# controller.net
KiCad netlist of a schematic drawn in Altium Designer
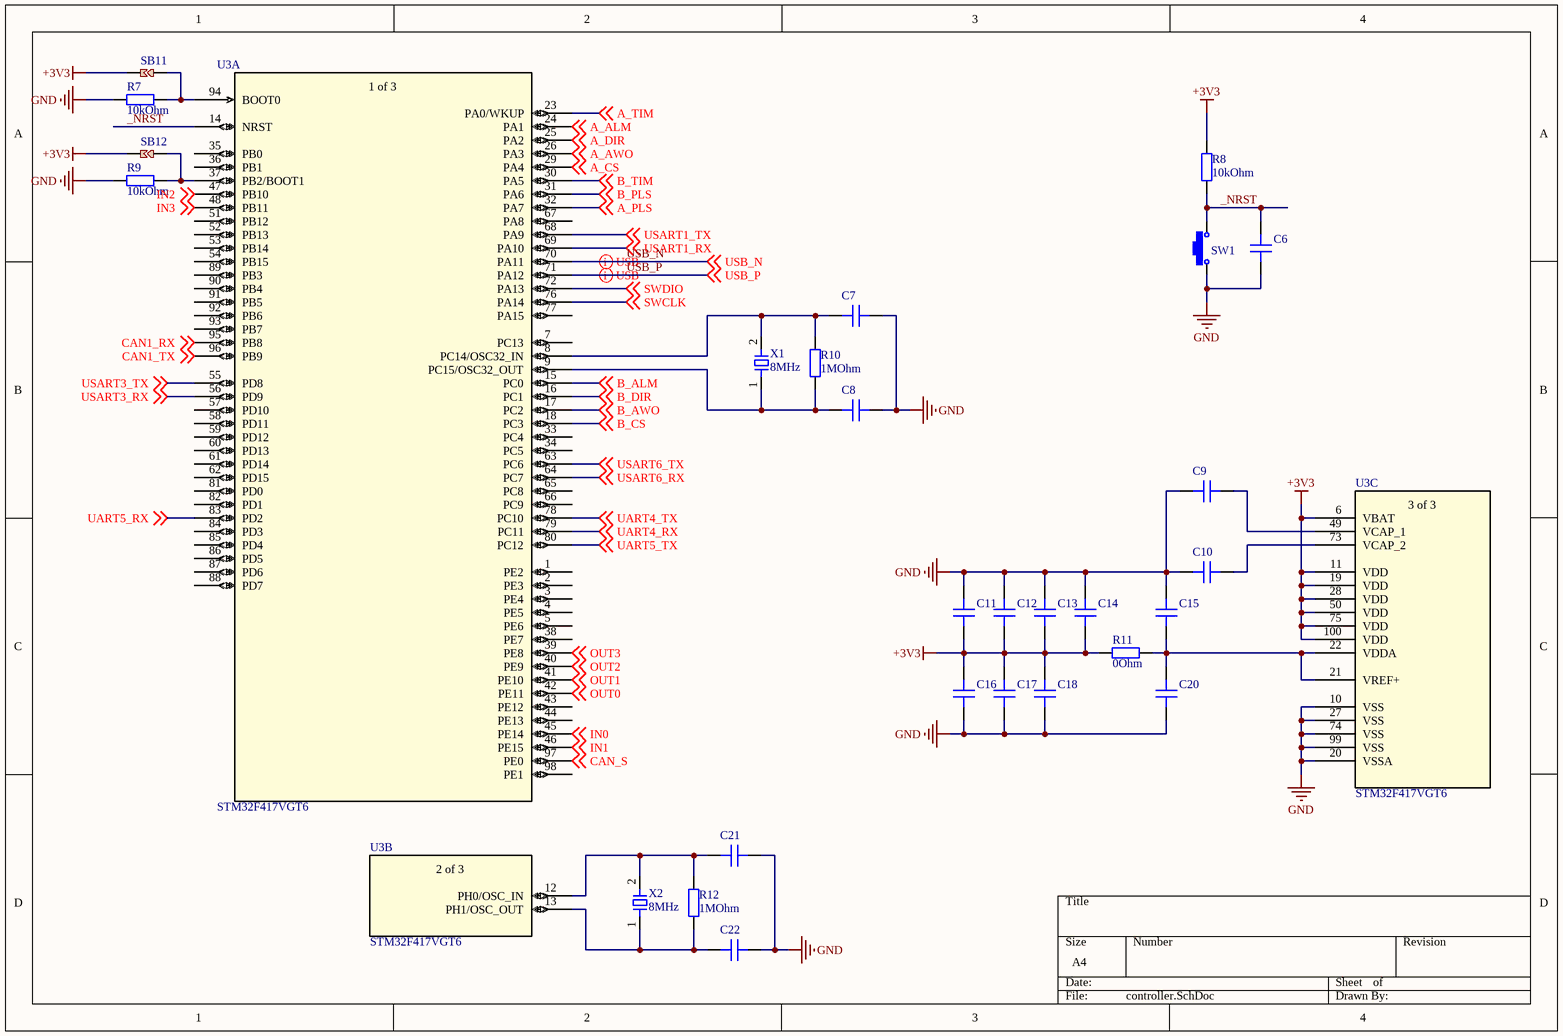
[diagram p0: controller.SchDoc]

(export (version "E")
  (design (tool "Eeschema 10.0.6"))
  (components
    (comp (ref "C6")
      (value "100nF")
      (footprint "CAP 0805")
      (description "Non-polar capacitor")
      (fields (field (name "PUBLISHER") "Altium Limited"))
      (libsource (lib "MiLib") (part "Cap"))
    )
    (comp (ref "C7")
      (value "100nF")
      (footprint "CAP 0805")
      (description "Non-polar capacitor")
      (fields (field (name "PUBLISHER") "Altium Limited"))
      (libsource (lib "MiLib") (part "Cap"))
    )
    (comp (ref "C8")
      (value "100nF")
      (footprint "CAP 0805")
      (description "Non-polar capacitor")
      (fields (field (name "PUBLISHER") "Altium Limited"))
      (libsource (lib "MiLib") (part "Cap"))
    )
    (comp (ref "C9")
      (value "100nF")
      (footprint "CAP 0805")
      (description "Non-polar capacitor")
      (fields (field (name "PUBLISHER") "Altium Limited"))
      (libsource (lib "MiLib") (part "Cap"))
    )
    (comp (ref "C10")
      (value "100nF")
      (footprint "CAP 0805")
      (description "Non-polar capacitor")
      (fields (field (name "PUBLISHER") "Altium Limited"))
      (libsource (lib "MiLib") (part "Cap"))
    )
    (comp (ref "C11")
      (value "100nF")
      (footprint "CAP 0805")
      (description "Non-polar capacitor")
      (fields (field (name "PUBLISHER") "Altium Limited"))
      (libsource (lib "MiLib") (part "Cap"))
    )
    (comp (ref "C12")
      (value "100nF")
      (footprint "CAP 0805")
      (description "Non-polar capacitor")
      (fields (field (name "PUBLISHER") "Altium Limited"))
      (libsource (lib "MiLib") (part "Cap"))
    )
    (comp (ref "C13")
      (value "100nF")
      (footprint "CAP 0805")
      (description "Non-polar capacitor")
      (fields (field (name "PUBLISHER") "Altium Limited"))
      (libsource (lib "MiLib") (part "Cap"))
    )
    (comp (ref "C14")
      (value "100nF")
      (footprint "CAP 0805")
      (description "Non-polar capacitor")
      (fields (field (name "PUBLISHER") "Altium Limited"))
      (libsource (lib "MiLib") (part "Cap"))
    )
    (comp (ref "C15")
      (value "100nF")
      (footprint "CAP 0805")
      (description "Non-polar capacitor")
      (fields (field (name "PUBLISHER") "Altium Limited"))
      (libsource (lib "MiLib") (part "Cap"))
    )
    (comp (ref "C16")
      (value "100nF")
      (footprint "CAP 0805")
      (description "Non-polar capacitor")
      (fields (field (name "PUBLISHER") "Altium Limited"))
      (libsource (lib "MiLib") (part "Cap"))
    )
    (comp (ref "C17")
      (value "100nF")
      (footprint "CAP 0805")
      (description "Non-polar capacitor")
      (fields (field (name "PUBLISHER") "Altium Limited"))
      (libsource (lib "MiLib") (part "Cap"))
    )
    (comp (ref "C18")
      (value "100nF")
      (footprint "CAP 0805")
      (description "Non-polar capacitor")
      (fields (field (name "PUBLISHER") "Altium Limited"))
      (libsource (lib "MiLib") (part "Cap"))
    )
    (comp (ref "C20")
      (value "100nF")
      (footprint "CAP 0805")
      (description "Non-polar capacitor")
      (fields (field (name "PUBLISHER") "Altium Limited"))
      (libsource (lib "MiLib") (part "Cap"))
    )
    (comp (ref "C21")
      (value "100nF")
      (footprint "CAP 0805")
      (description "Non-polar capacitor")
      (fields (field (name "PUBLISHER") "Altium Limited"))
      (libsource (lib "MiLib") (part "Cap"))
    )
    (comp (ref "C22")
      (value "100nF")
      (footprint "CAP 0805")
      (description "Non-polar capacitor")
      (fields (field (name "PUBLISHER") "Altium Limited"))
      (libsource (lib "MiLib") (part "Cap"))
    )
    (comp (ref "R7")
      (value "10kOhm")
      (footprint "RES 0805")
      (description "Resistor")
      (fields (field (name "PUBLISHER") "Altium Limited"))
      (libsource (lib "") (part "Res_1"))
    )
    (comp (ref "R8")
      (value "10kOhm")
      (footprint "RES 0805")
      (description "Resistor")
      (fields (field (name "PUBLISHER") "Altium Limited"))
      (libsource (lib "MiLib") (part "Res"))
    )
    (comp (ref "R9")
      (value "10kOhm")
      (footprint "RES 0805")
      (description "Resistor")
      (fields (field (name "PUBLISHER") "Altium Limited"))
      (libsource (lib "") (part "Res_1"))
    )
    (comp (ref "R10")
      (value "1MOhm")
      (footprint "RES 0805")
      (description "Resistor")
      (fields (field (name "PUBLISHER") "Altium Limited"))
      (libsource (lib "MiLib") (part "Res"))
    )
    (comp (ref "R11")
      (value "0Ohm")
      (footprint "RES 0805")
      (description "Resistor")
      (fields (field (name "PUBLISHER") "Altium Limited"))
      (libsource (lib "") (part "Res_2"))
    )
    (comp (ref "R12")
      (value "1MOhm")
      (footprint "RES 0805")
      (description "Resistor")
      (fields (field (name "PUBLISHER") "Altium Limited"))
      (libsource (lib "MiLib") (part "Res"))
    )
    (comp (ref "SB11") (value "SB") (footprint "Solder Bridge") (libsource (lib "MiLib") (part "SB")))
    (comp (ref "SB12") (value "SB") (footprint "Solder Bridge") (libsource (lib "MiLib") (part "SB")))
    (comp (ref "SW1")
      (value "Button")
      (footprint "TSW SMD-3*6*2.5")
      (fields (field (name "版权归属") "黎明电子style"))
      (libsource (lib "MiLib") (part "BTN"))
    )
    (comp (ref "U3")
      (value "STM32F417VGT6")
      (footprint "LQFP100-14×14mm")
      (description "No Description Available")
      (fields (field (name "COPYRIGHT") "Copyright (C) 2018 Accelerated Designs. All rights reserved"))
      (libsource (lib "misc") (part "STM32F417VGT6"))
    )
    (comp (ref "X1")
      (value "8MHz")
      (footprint "XTAL 3215")
      (description "Passive Oscillator")
      (fields (field (name "版权归属") "黎明电子style"))
      (libsource (lib "MiLib") (part "XTAL"))
    )
    (comp (ref "X2")
      (value "8MHz")
      (footprint "XTAL 3225")
      (description "Passive Oscillator")
      (fields (field (name "版权归属") "黎明电子style"))
      (libsource (lib "MiLib") (part "XTAL"))
    )
  )
  (nets
    (net (code "1") (name "+3V3") (class "Default")
      (node (ref "C11") (pin "1") (pinfunction "1_1") (pintype "passive"))
      (node (ref "C12") (pin "1") (pinfunction "1_1") (pintype "passive"))
      (node (ref "C13") (pin "1") (pinfunction "1_1") (pintype "passive"))
      (node (ref "C14") (pin "1") (pinfunction "1_1") (pintype "passive"))
      (node (ref "C16") (pin "2") (pinfunction "2_2") (pintype "passive"))
      (node (ref "C17") (pin "2") (pinfunction "2_2") (pintype "passive"))
      (node (ref "C18") (pin "2") (pinfunction "2_2") (pintype "passive"))
      (node (ref "R11") (pin "1") (pinfunction "1_1") (pintype "passive"))
      (node (ref "R8") (pin "2") (pinfunction "2_2") (pintype "passive"))
      (node (ref "SB11") (pin "1") (pinfunction "1_1") (pintype "passive"))
      (node (ref "SB12") (pin "1") (pinfunction "1_1") (pintype "passive"))
      (node (ref "U3") (pin "100") (pinfunction "VDD_100") (pintype "power_in"))
      (node (ref "U3") (pin "11") (pinfunction "VDD_11") (pintype "power_in"))
      (node (ref "U3") (pin "19") (pinfunction "VDD_19") (pintype "power_in"))
      (node (ref "U3") (pin "28") (pinfunction "VDD_28") (pintype "power_in"))
      (node (ref "U3") (pin "50") (pinfunction "VDD_50") (pintype "power_in"))
      (node (ref "U3") (pin "6") (pinfunction "VBAT_6") (pintype "power_in"))
      (node (ref "U3") (pin "75") (pinfunction "VDD_75") (pintype "power_in"))
    )
    (net (code "2") (name "/_NRST") (class "Default")
      (node (ref "C6") (pin "2") (pinfunction "2_2") (pintype "passive"))
      (node (ref "R8") (pin "1") (pinfunction "1_1") (pintype "passive"))
      (node (ref "SW1") (pin "2") (pinfunction "2_2") (pintype "passive"))
      (node (ref "U3") (pin "14") (pinfunction "NRST_14") (pintype "bidirectional"))
    )
    (net (code "3") (name "A_ALM") (class "Default")
      (node (ref "U3") (pin "24") (pinfunction "PA1_24") (pintype "bidirectional"))
    )
    (net (code "4") (name "A_AWO") (class "Default")
      (node (ref "U3") (pin "26") (pinfunction "PA3_26") (pintype "bidirectional"))
    )
    (net (code "5") (name "A_CS") (class "Default")
      (node (ref "U3") (pin "29") (pinfunction "PA4_29") (pintype "bidirectional"))
    )
    (net (code "6") (name "A_DIR") (class "Default")
      (node (ref "U3") (pin "25") (pinfunction "PA2_25") (pintype "bidirectional"))
    )
    (net (code "7") (name "A_PLS") (class "Default")
      (node (ref "U3") (pin "32") (pinfunction "PA7_32") (pintype "bidirectional"))
    )
    (net (code "8") (name "A_TIM") (class "Default")
      (node (ref "U3") (pin "23") (pinfunction "PA0/WKUP_23") (pintype "bidirectional"))
    )
    (net (code "9") (name "B_ALM") (class "Default")
      (node (ref "U3") (pin "15") (pinfunction "PC0_15") (pintype "bidirectional"))
    )
    (net (code "10") (name "B_AWO") (class "Default")
      (node (ref "U3") (pin "17") (pinfunction "PC2_17") (pintype "bidirectional"))
    )
    (net (code "11") (name "B_CS") (class "Default")
      (node (ref "U3") (pin "18") (pinfunction "PC3_18") (pintype "bidirectional"))
    )
    (net (code "12") (name "B_DIR") (class "Default")
      (node (ref "U3") (pin "16") (pinfunction "PC1_16") (pintype "bidirectional"))
    )
    (net (code "13") (name "B_PLS") (class "Default")
      (node (ref "U3") (pin "31") (pinfunction "PA6_31") (pintype "bidirectional"))
    )
    (net (code "14") (name "B_TIM") (class "Default")
      (node (ref "U3") (pin "30") (pinfunction "PA5_30") (pintype "bidirectional"))
    )
    (net (code "15") (name "CAN1_RX") (class "Default")
      (node (ref "U3") (pin "95") (pinfunction "PB8_95") (pintype "bidirectional"))
    )
    (net (code "16") (name "CAN1_TX") (class "Default")
      (node (ref "U3") (pin "96") (pinfunction "PB9_96") (pintype "bidirectional"))
    )
    (net (code "17") (name "CAN_S") (class "Default")
      (node (ref "U3") (pin "97") (pinfunction "PE0_97") (pintype "bidirectional"))
    )
    (net (code "18") (name "GND") (class "Default")
      (node (ref "C10") (pin "2") (pinfunction "2_2") (pintype "passive"))
      (node (ref "C11") (pin "2") (pinfunction "2_2") (pintype "passive"))
      (node (ref "C12") (pin "2") (pinfunction "2_2") (pintype "passive"))
      (node (ref "C13") (pin "2") (pinfunction "2_2") (pintype "passive"))
      (node (ref "C14") (pin "2") (pinfunction "2_2") (pintype "passive"))
      (node (ref "C15") (pin "2") (pinfunction "2_2") (pintype "passive"))
      (node (ref "C16") (pin "1") (pinfunction "1_1") (pintype "passive"))
      (node (ref "C17") (pin "1") (pinfunction "1_1") (pintype "passive"))
      (node (ref "C18") (pin "1") (pinfunction "1_1") (pintype "passive"))
      (node (ref "C20") (pin "1") (pinfunction "1_1") (pintype "passive"))
      (node (ref "C21") (pin "2") (pinfunction "2_2") (pintype "passive"))
      (node (ref "C22") (pin "2") (pinfunction "2_2") (pintype "passive"))
      (node (ref "C6") (pin "1") (pinfunction "1_1") (pintype "passive"))
      (node (ref "C7") (pin "2") (pinfunction "2_2") (pintype "passive"))
      (node (ref "C8") (pin "2") (pinfunction "2_2") (pintype "passive"))
      (node (ref "C9") (pin "2") (pinfunction "2_2") (pintype "passive"))
      (node (ref "R7") (pin "2") (pinfunction "2_2") (pintype "passive"))
      (node (ref "R9") (pin "2") (pinfunction "2_2") (pintype "passive"))
      (node (ref "SW1") (pin "1") (pinfunction "1_1") (pintype "passive"))
      (node (ref "U3") (pin "10") (pinfunction "VSS_10") (pintype "power_in"))
      (node (ref "U3") (pin "20") (pinfunction "VSSA_20") (pintype "power_in"))
      (node (ref "U3") (pin "27") (pinfunction "VSS_27") (pintype "power_in"))
      (node (ref "U3") (pin "74") (pinfunction "VSS_74") (pintype "power_in"))
      (node (ref "U3") (pin "99") (pinfunction "VSS_99") (pintype "power_in"))
    )
    (net (code "19") (name "IN0") (class "Default")
      (node (ref "U3") (pin "45") (pinfunction "PE14_45") (pintype "bidirectional"))
    )
    (net (code "20") (name "IN1") (class "Default")
      (node (ref "U3") (pin "46") (pinfunction "PE15_46") (pintype "bidirectional"))
    )
    (net (code "21") (name "IN2") (class "Default")
      (node (ref "U3") (pin "47") (pinfunction "PB10_47") (pintype "bidirectional"))
    )
    (net (code "22") (name "IN3") (class "Default")
      (node (ref "U3") (pin "48") (pinfunction "PB11_48") (pintype "bidirectional"))
    )
    (net (code "23") (name "Net-(U3A-BOOT0)") (class "Default")
      (node (ref "R7") (pin "1") (pinfunction "1_1") (pintype "passive"))
      (node (ref "SB11") (pin "2") (pinfunction "2_2") (pintype "passive"))
      (node (ref "U3") (pin "94") (pinfunction "BOOT0_94") (pintype "input"))
    )
    (net (code "24") (name "Net-(U3A-PB2{slash}BOOT1)") (class "Default")
      (node (ref "R9") (pin "1") (pinfunction "1_1") (pintype "passive"))
      (node (ref "SB12") (pin "2") (pinfunction "2_2") (pintype "passive"))
      (node (ref "U3") (pin "37") (pinfunction "PB2/BOOT1_37") (pintype "bidirectional"))
    )
    (net (code "25") (name "Net-(U3A-PC14{slash}OSC32_IN)") (class "Default")
      (node (ref "C7") (pin "1") (pinfunction "1_1") (pintype "passive"))
      (node (ref "R10") (pin "2") (pinfunction "2_2") (pintype "passive"))
      (node (ref "U3") (pin "8") (pinfunction "PC14/OSC32_IN_8") (pintype "bidirectional"))
      (node (ref "X1") (pin "2") (pinfunction "2_2") (pintype "passive"))
    )
    (net (code "26") (name "Net-(U3A-PC15{slash}OSC32_OUT)") (class "Default")
      (node (ref "C8") (pin "1") (pinfunction "1_1") (pintype "passive"))
      (node (ref "R10") (pin "1") (pinfunction "1_1") (pintype "passive"))
      (node (ref "U3") (pin "9") (pinfunction "PC15/OSC32_OUT_9") (pintype "bidirectional"))
      (node (ref "X1") (pin "1") (pinfunction "1_1") (pintype "passive"))
    )
    (net (code "27") (name "Net-(U3B-PH0{slash}OSC_IN)") (class "Default")
      (node (ref "C21") (pin "1") (pinfunction "1_1") (pintype "passive"))
      (node (ref "R12") (pin "2") (pinfunction "2_2") (pintype "passive"))
      (node (ref "U3") (pin "12") (pinfunction "PH0/OSC_IN_12") (pintype "bidirectional"))
      (node (ref "X2") (pin "2") (pinfunction "2_2") (pintype "passive"))
    )
    (net (code "28") (name "Net-(U3B-PH1{slash}OSC_OUT)") (class "Default")
      (node (ref "C22") (pin "1") (pinfunction "1_1") (pintype "passive"))
      (node (ref "R12") (pin "1") (pinfunction "1_1") (pintype "passive"))
      (node (ref "U3") (pin "13") (pinfunction "PH1/OSC_OUT_13") (pintype "bidirectional"))
      (node (ref "X2") (pin "1") (pinfunction "1_1") (pintype "passive"))
    )
    (net (code "29") (name "Net-(U3C-VCAP_1)") (class "Default")
      (node (ref "C9") (pin "1") (pinfunction "1_1") (pintype "passive"))
      (node (ref "U3") (pin "49") (pinfunction "VCAP_1_49") (pintype "power_in"))
    )
    (net (code "30") (name "Net-(U3C-VCAP_2)") (class "Default")
      (node (ref "C10") (pin "1") (pinfunction "1_1") (pintype "passive"))
      (node (ref "U3") (pin "73") (pinfunction "VCAP_2_73") (pintype "power_in"))
    )
    (net (code "31") (name "Net-(U3C-VDDA)") (class "Default")
      (node (ref "C15") (pin "1") (pinfunction "1_1") (pintype "passive"))
      (node (ref "C20") (pin "2") (pinfunction "2_2") (pintype "passive"))
      (node (ref "R11") (pin "2") (pinfunction "2_2") (pintype "passive"))
      (node (ref "U3") (pin "21") (pinfunction "VREF+_21") (pintype "power_in"))
      (node (ref "U3") (pin "22") (pinfunction "VDDA_22") (pintype "power_in"))
    )
    (net (code "32") (name "OUT0") (class "Default")
      (node (ref "U3") (pin "42") (pinfunction "PE11_42") (pintype "bidirectional"))
    )
    (net (code "33") (name "OUT1") (class "Default")
      (node (ref "U3") (pin "41") (pinfunction "PE10_41") (pintype "bidirectional"))
    )
    (net (code "34") (name "OUT2") (class "Default")
      (node (ref "U3") (pin "40") (pinfunction "PE9_40") (pintype "bidirectional"))
    )
    (net (code "35") (name "OUT3") (class "Default")
      (node (ref "U3") (pin "39") (pinfunction "PE8_39") (pintype "bidirectional"))
    )
    (net (code "36") (name "SWCLK") (class "Default")
      (node (ref "U3") (pin "76") (pinfunction "PA14_76") (pintype "bidirectional"))
    )
    (net (code "37") (name "SWDIO") (class "Default")
      (node (ref "U3") (pin "72") (pinfunction "PA13_72") (pintype "bidirectional"))
    )
    (net (code "38") (name "UART4_RX") (class "Default")
      (node (ref "U3") (pin "79") (pinfunction "PC11_79") (pintype "bidirectional"))
    )
    (net (code "39") (name "UART4_TX") (class "Default")
      (node (ref "U3") (pin "78") (pinfunction "PC10_78") (pintype "bidirectional"))
    )
    (net (code "40") (name "UART5_RX") (class "Default")
      (node (ref "U3") (pin "83") (pinfunction "PD2_83") (pintype "bidirectional"))
    )
    (net (code "41") (name "UART5_TX") (class "Default")
      (node (ref "U3") (pin "80") (pinfunction "PC12_80") (pintype "bidirectional"))
    )
    (net (code "42") (name "USART1_RX") (class "Default")
      (node (ref "U3") (pin "69") (pinfunction "PA10_69") (pintype "bidirectional"))
    )
    (net (code "43") (name "USART1_TX") (class "Default")
      (node (ref "U3") (pin "68") (pinfunction "PA9_68") (pintype "bidirectional"))
    )
    (net (code "44") (name "USART3_RX") (class "Default")
      (node (ref "U3") (pin "56") (pinfunction "PD9_56") (pintype "bidirectional"))
    )
    (net (code "45") (name "USART3_TX") (class "Default")
      (node (ref "U3") (pin "55") (pinfunction "PD8_55") (pintype "bidirectional"))
    )
    (net (code "46") (name "USART6_RX") (class "Default")
      (node (ref "U3") (pin "64") (pinfunction "PC7_64") (pintype "bidirectional"))
    )
    (net (code "47") (name "USART6_TX") (class "Default")
      (node (ref "U3") (pin "63") (pinfunction "PC6_63") (pintype "bidirectional"))
    )
    (net (code "48") (name "USB_N") (class "Default")
      (node (ref "U3") (pin "70") (pinfunction "PA11_70") (pintype "bidirectional"))
    )
    (net (code "49") (name "USB_P") (class "Default")
      (node (ref "U3") (pin "71") (pinfunction "PA12_71") (pintype "bidirectional"))
    )
    (net (code "50") (name "unconnected-(U3A-PA8-Pad67)") (class "Default")
      (node (ref "U3") (pin "67") (pinfunction "PA8_67") (pintype "bidirectional"))
    )
    (net (code "51") (name "unconnected-(U3A-PA15-Pad77)") (class "Default")
      (node (ref "U3") (pin "77") (pinfunction "PA15_77") (pintype "bidirectional"))
    )
    (net (code "52") (name "unconnected-(U3A-PB0-Pad35)") (class "Default")
      (node (ref "U3") (pin "35") (pinfunction "PB0_35") (pintype "bidirectional"))
    )
    (net (code "53") (name "unconnected-(U3A-PB1-Pad36)") (class "Default")
      (node (ref "U3") (pin "36") (pinfunction "PB1_36") (pintype "bidirectional"))
    )
    (net (code "54") (name "unconnected-(U3A-PB3-Pad89)") (class "Default")
      (node (ref "U3") (pin "89") (pinfunction "PB3_89") (pintype "bidirectional"))
    )
    (net (code "55") (name "unconnected-(U3A-PB4-Pad90)") (class "Default")
      (node (ref "U3") (pin "90") (pinfunction "PB4_90") (pintype "bidirectional"))
    )
    (net (code "56") (name "unconnected-(U3A-PB5-Pad91)") (class "Default")
      (node (ref "U3") (pin "91") (pinfunction "PB5_91") (pintype "bidirectional"))
    )
    (net (code "57") (name "unconnected-(U3A-PB6-Pad92)") (class "Default")
      (node (ref "U3") (pin "92") (pinfunction "PB6_92") (pintype "bidirectional"))
    )
    (net (code "58") (name "unconnected-(U3A-PB7-Pad93)") (class "Default")
      (node (ref "U3") (pin "93") (pinfunction "PB7_93") (pintype "bidirectional"))
    )
    (net (code "59") (name "unconnected-(U3A-PB12-Pad51)") (class "Default")
      (node (ref "U3") (pin "51") (pinfunction "PB12_51") (pintype "bidirectional"))
    )
    (net (code "60") (name "unconnected-(U3A-PB13-Pad52)") (class "Default")
      (node (ref "U3") (pin "52") (pinfunction "PB13_52") (pintype "bidirectional"))
    )
    (net (code "61") (name "unconnected-(U3A-PB14-Pad53)") (class "Default")
      (node (ref "U3") (pin "53") (pinfunction "PB14_53") (pintype "bidirectional"))
    )
    (net (code "62") (name "unconnected-(U3A-PB15-Pad54)") (class "Default")
      (node (ref "U3") (pin "54") (pinfunction "PB15_54") (pintype "bidirectional"))
    )
    (net (code "63") (name "unconnected-(U3A-PC4-Pad33)") (class "Default")
      (node (ref "U3") (pin "33") (pinfunction "PC4_33") (pintype "bidirectional"))
    )
    (net (code "64") (name "unconnected-(U3A-PC5-Pad34)") (class "Default")
      (node (ref "U3") (pin "34") (pinfunction "PC5_34") (pintype "bidirectional"))
    )
    (net (code "65") (name "unconnected-(U3A-PC8-Pad65)") (class "Default")
      (node (ref "U3") (pin "65") (pinfunction "PC8_65") (pintype "bidirectional"))
    )
    (net (code "66") (name "unconnected-(U3A-PC9-Pad66)") (class "Default")
      (node (ref "U3") (pin "66") (pinfunction "PC9_66") (pintype "bidirectional"))
    )
    (net (code "67") (name "unconnected-(U3A-PC13-Pad7)") (class "Default")
      (node (ref "U3") (pin "7") (pinfunction "PC13_7") (pintype "bidirectional"))
    )
    (net (code "68") (name "unconnected-(U3A-PD0-Pad81)") (class "Default")
      (node (ref "U3") (pin "81") (pinfunction "PD0_81") (pintype "bidirectional"))
    )
    (net (code "69") (name "unconnected-(U3A-PD1-Pad82)") (class "Default")
      (node (ref "U3") (pin "82") (pinfunction "PD1_82") (pintype "bidirectional"))
    )
    (net (code "70") (name "unconnected-(U3A-PD3-Pad84)") (class "Default")
      (node (ref "U3") (pin "84") (pinfunction "PD3_84") (pintype "bidirectional"))
    )
    (net (code "71") (name "unconnected-(U3A-PD4-Pad85)") (class "Default")
      (node (ref "U3") (pin "85") (pinfunction "PD4_85") (pintype "bidirectional"))
    )
    (net (code "72") (name "unconnected-(U3A-PD5-Pad86)") (class "Default")
      (node (ref "U3") (pin "86") (pinfunction "PD5_86") (pintype "bidirectional"))
    )
    (net (code "73") (name "unconnected-(U3A-PD6-Pad87)") (class "Default")
      (node (ref "U3") (pin "87") (pinfunction "PD6_87") (pintype "bidirectional"))
    )
    (net (code "74") (name "unconnected-(U3A-PD7-Pad88)") (class "Default")
      (node (ref "U3") (pin "88") (pinfunction "PD7_88") (pintype "bidirectional"))
    )
    (net (code "75") (name "unconnected-(U3A-PD10-Pad57)") (class "Default")
      (node (ref "U3") (pin "57") (pinfunction "PD10_57") (pintype "bidirectional"))
    )
    (net (code "76") (name "unconnected-(U3A-PD11-Pad58)") (class "Default")
      (node (ref "U3") (pin "58") (pinfunction "PD11_58") (pintype "bidirectional"))
    )
    (net (code "77") (name "unconnected-(U3A-PD12-Pad59)") (class "Default")
      (node (ref "U3") (pin "59") (pinfunction "PD12_59") (pintype "bidirectional"))
    )
    (net (code "78") (name "unconnected-(U3A-PD13-Pad60)") (class "Default")
      (node (ref "U3") (pin "60") (pinfunction "PD13_60") (pintype "bidirectional"))
    )
    (net (code "79") (name "unconnected-(U3A-PD14-Pad61)") (class "Default")
      (node (ref "U3") (pin "61") (pinfunction "PD14_61") (pintype "bidirectional"))
    )
    (net (code "80") (name "unconnected-(U3A-PD15-Pad62)") (class "Default")
      (node (ref "U3") (pin "62") (pinfunction "PD15_62") (pintype "bidirectional"))
    )
    (net (code "81") (name "unconnected-(U3A-PE1-Pad98)") (class "Default")
      (node (ref "U3") (pin "98") (pinfunction "PE1_98") (pintype "bidirectional"))
    )
    (net (code "82") (name "unconnected-(U3A-PE2-Pad1)") (class "Default")
      (node (ref "U3") (pin "1") (pinfunction "PE2_1") (pintype "bidirectional"))
    )
    (net (code "83") (name "unconnected-(U3A-PE3-Pad2)") (class "Default")
      (node (ref "U3") (pin "2") (pinfunction "PE3_2") (pintype "bidirectional"))
    )
    (net (code "84") (name "unconnected-(U3A-PE4-Pad3)") (class "Default")
      (node (ref "U3") (pin "3") (pinfunction "PE4_3") (pintype "bidirectional"))
    )
    (net (code "85") (name "unconnected-(U3A-PE5-Pad4)") (class "Default")
      (node (ref "U3") (pin "4") (pinfunction "PE5_4") (pintype "bidirectional"))
    )
    (net (code "86") (name "unconnected-(U3A-PE6-Pad5)") (class "Default")
      (node (ref "U3") (pin "5") (pinfunction "PE6_5") (pintype "bidirectional"))
    )
    (net (code "87") (name "unconnected-(U3A-PE7-Pad38)") (class "Default")
      (node (ref "U3") (pin "38") (pinfunction "PE7_38") (pintype "bidirectional"))
    )
    (net (code "88") (name "unconnected-(U3A-PE12-Pad43)") (class "Default")
      (node (ref "U3") (pin "43") (pinfunction "PE12_43") (pintype "bidirectional"))
    )
    (net (code "89") (name "unconnected-(U3A-PE13-Pad44)") (class "Default")
      (node (ref "U3") (pin "44") (pinfunction "PE13_44") (pintype "bidirectional"))
    )
  )
)
